# TS4994_Add_on_v1.net
KiCad netlist of a schematic drawn in Altium Designer
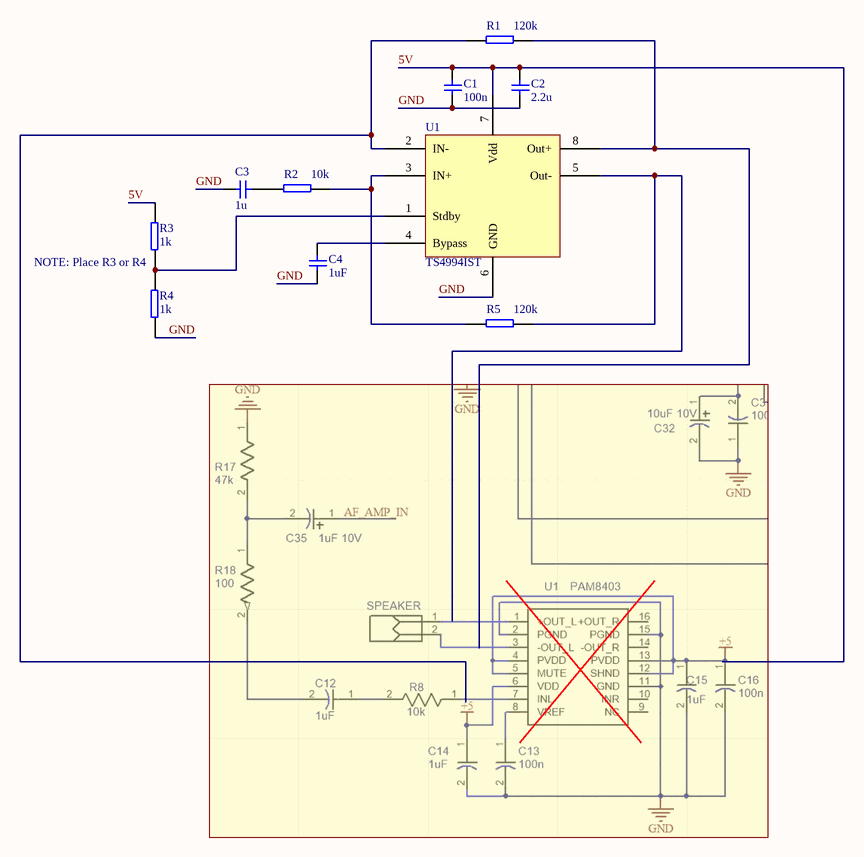
[diagram p0: TS4994_Add_on_v1.SchDoc]

(export (version "E")
  (design (tool "Eeschema 10.0.6"))
  (components
    (comp (ref "C1")
      (value "100n")
      (footprint "0805S")
      (description "Capacitor")
      (fields (field (name "Comment") "C0805"))
      (libsource (lib "Ivan DXP SCH LIB") (part "C0805"))
    )
    (comp (ref "C2")
      (value "2.2u")
      (footprint "0805S")
      (description "Capacitor")
      (fields (field (name "Comment") "C0805"))
      (libsource (lib "Ivan DXP SCH LIB") (part "C0805"))
    )
    (comp (ref "C3")
      (value "1u")
      (footprint "0805S")
      (description "Capacitor")
      (fields (field (name "Comment") "C0805"))
      (libsource (lib "Ivan DXP SCH LIB") (part "C0805"))
    )
    (comp (ref "C4")
      (value "1uF")
      (footprint "0805S")
      (description "Capacitor")
      (fields (field (name "Comment") "C0805"))
      (libsource (lib "Ivan DXP SCH LIB") (part "C0805"))
    )
    (comp (ref "R1")
      (value "120k")
      (footprint "0805S")
      (description "Resistor")
      (fields (field (name "Comment") "R0805"))
      (libsource (lib "") (part "R0805_1"))
    )
    (comp (ref "R2")
      (value "10k")
      (footprint "0805S")
      (description "Resistor")
      (fields (field (name "Comment") "R0805"))
      (libsource (lib "") (part "R0805_1"))
    )
    (comp (ref "R3")
      (value "1k")
      (footprint "0805S")
      (description "Resistor")
      (fields (field (name "Comment") "R0805"))
      (libsource (lib "Ivan DXP SCH LIB") (part "R0805"))
    )
    (comp (ref "R4")
      (value "1k")
      (footprint "0805S")
      (description "Resistor")
      (fields (field (name "Comment") "R0805"))
      (libsource (lib "Ivan DXP SCH LIB") (part "R0805"))
    )
    (comp (ref "R5")
      (value "120k")
      (footprint "0805S")
      (description "Resistor")
      (fields (field (name "Comment") "R0805"))
      (libsource (lib "") (part "R0805_1"))
    )
    (comp (ref "U1")
      (value "TS4994IST")
      (footprint "MSOP8")
      (libsource (lib "TeensySDR_Lib") (part "TS4994IST"))
    )
  )
  (nets
    (net (code "1") (name "/5V") (class "Default")
      (node (ref "C1") (pin "2") (pinfunction "2_2") (pintype "passive"))
      (node (ref "C2") (pin "2") (pinfunction "2_2") (pintype "passive"))
      (node (ref "R3") (pin "2") (pinfunction "2_2") (pintype "passive"))
      (node (ref "U1") (pin "7") (pinfunction "Vdd_7") (pintype "passive"))
    )
    (net (code "2") (name "/GND") (class "Default")
      (node (ref "C1") (pin "1") (pinfunction "1_1") (pintype "passive"))
      (node (ref "C2") (pin "1") (pinfunction "1_1") (pintype "passive"))
      (node (ref "C3") (pin "1") (pinfunction "1_1") (pintype "passive"))
      (node (ref "C4") (pin "1") (pinfunction "1_1") (pintype "passive"))
      (node (ref "R4") (pin "1") (pinfunction "1_1") (pintype "passive"))
      (node (ref "U1") (pin "6") (pinfunction "GND_6") (pintype "passive"))
    )
    (net (code "3") (name "Net-(C3-Pad2)") (class "Default")
      (node (ref "C3") (pin "2") (pinfunction "2_2") (pintype "passive"))
      (node (ref "R2") (pin "1") (pinfunction "1_1") (pintype "passive"))
    )
    (net (code "4") (name "Net-(U1-Bypass)") (class "Default")
      (node (ref "C4") (pin "2") (pinfunction "2_2") (pintype "passive"))
      (node (ref "U1") (pin "4") (pinfunction "Bypass_4") (pintype "passive"))
    )
    (net (code "5") (name "Net-(U1-IN+)") (class "Default")
      (node (ref "R2") (pin "2") (pinfunction "2_2") (pintype "passive"))
      (node (ref "R5") (pin "1") (pinfunction "1_1") (pintype "passive"))
      (node (ref "U1") (pin "3") (pinfunction "IN+_3") (pintype "passive"))
    )
    (net (code "6") (name "Net-(U1-IN-)") (class "Default")
      (node (ref "R1") (pin "1") (pinfunction "1_1") (pintype "passive"))
      (node (ref "U1") (pin "2") (pinfunction "IN-_2") (pintype "passive"))
    )
    (net (code "7") (name "Net-(U1-Out+)") (class "Default")
      (node (ref "R1") (pin "2") (pinfunction "2_2") (pintype "passive"))
      (node (ref "U1") (pin "8") (pinfunction "Out+_8") (pintype "passive"))
    )
    (net (code "8") (name "Net-(U1-Out-)") (class "Default")
      (node (ref "R5") (pin "2") (pinfunction "2_2") (pintype "passive"))
      (node (ref "U1") (pin "5") (pinfunction "Out-_5") (pintype "passive"))
    )
    (net (code "9") (name "Net-(U1-Stdby)") (class "Default")
      (node (ref "R3") (pin "1") (pinfunction "1_1") (pintype "passive"))
      (node (ref "R4") (pin "2") (pinfunction "2_2") (pintype "passive"))
      (node (ref "U1") (pin "1") (pinfunction "Stdby_1") (pintype "passive"))
    )
  )
)
